# main_scheme.net
KiCad netlist of a schematic drawn in Altium Designer
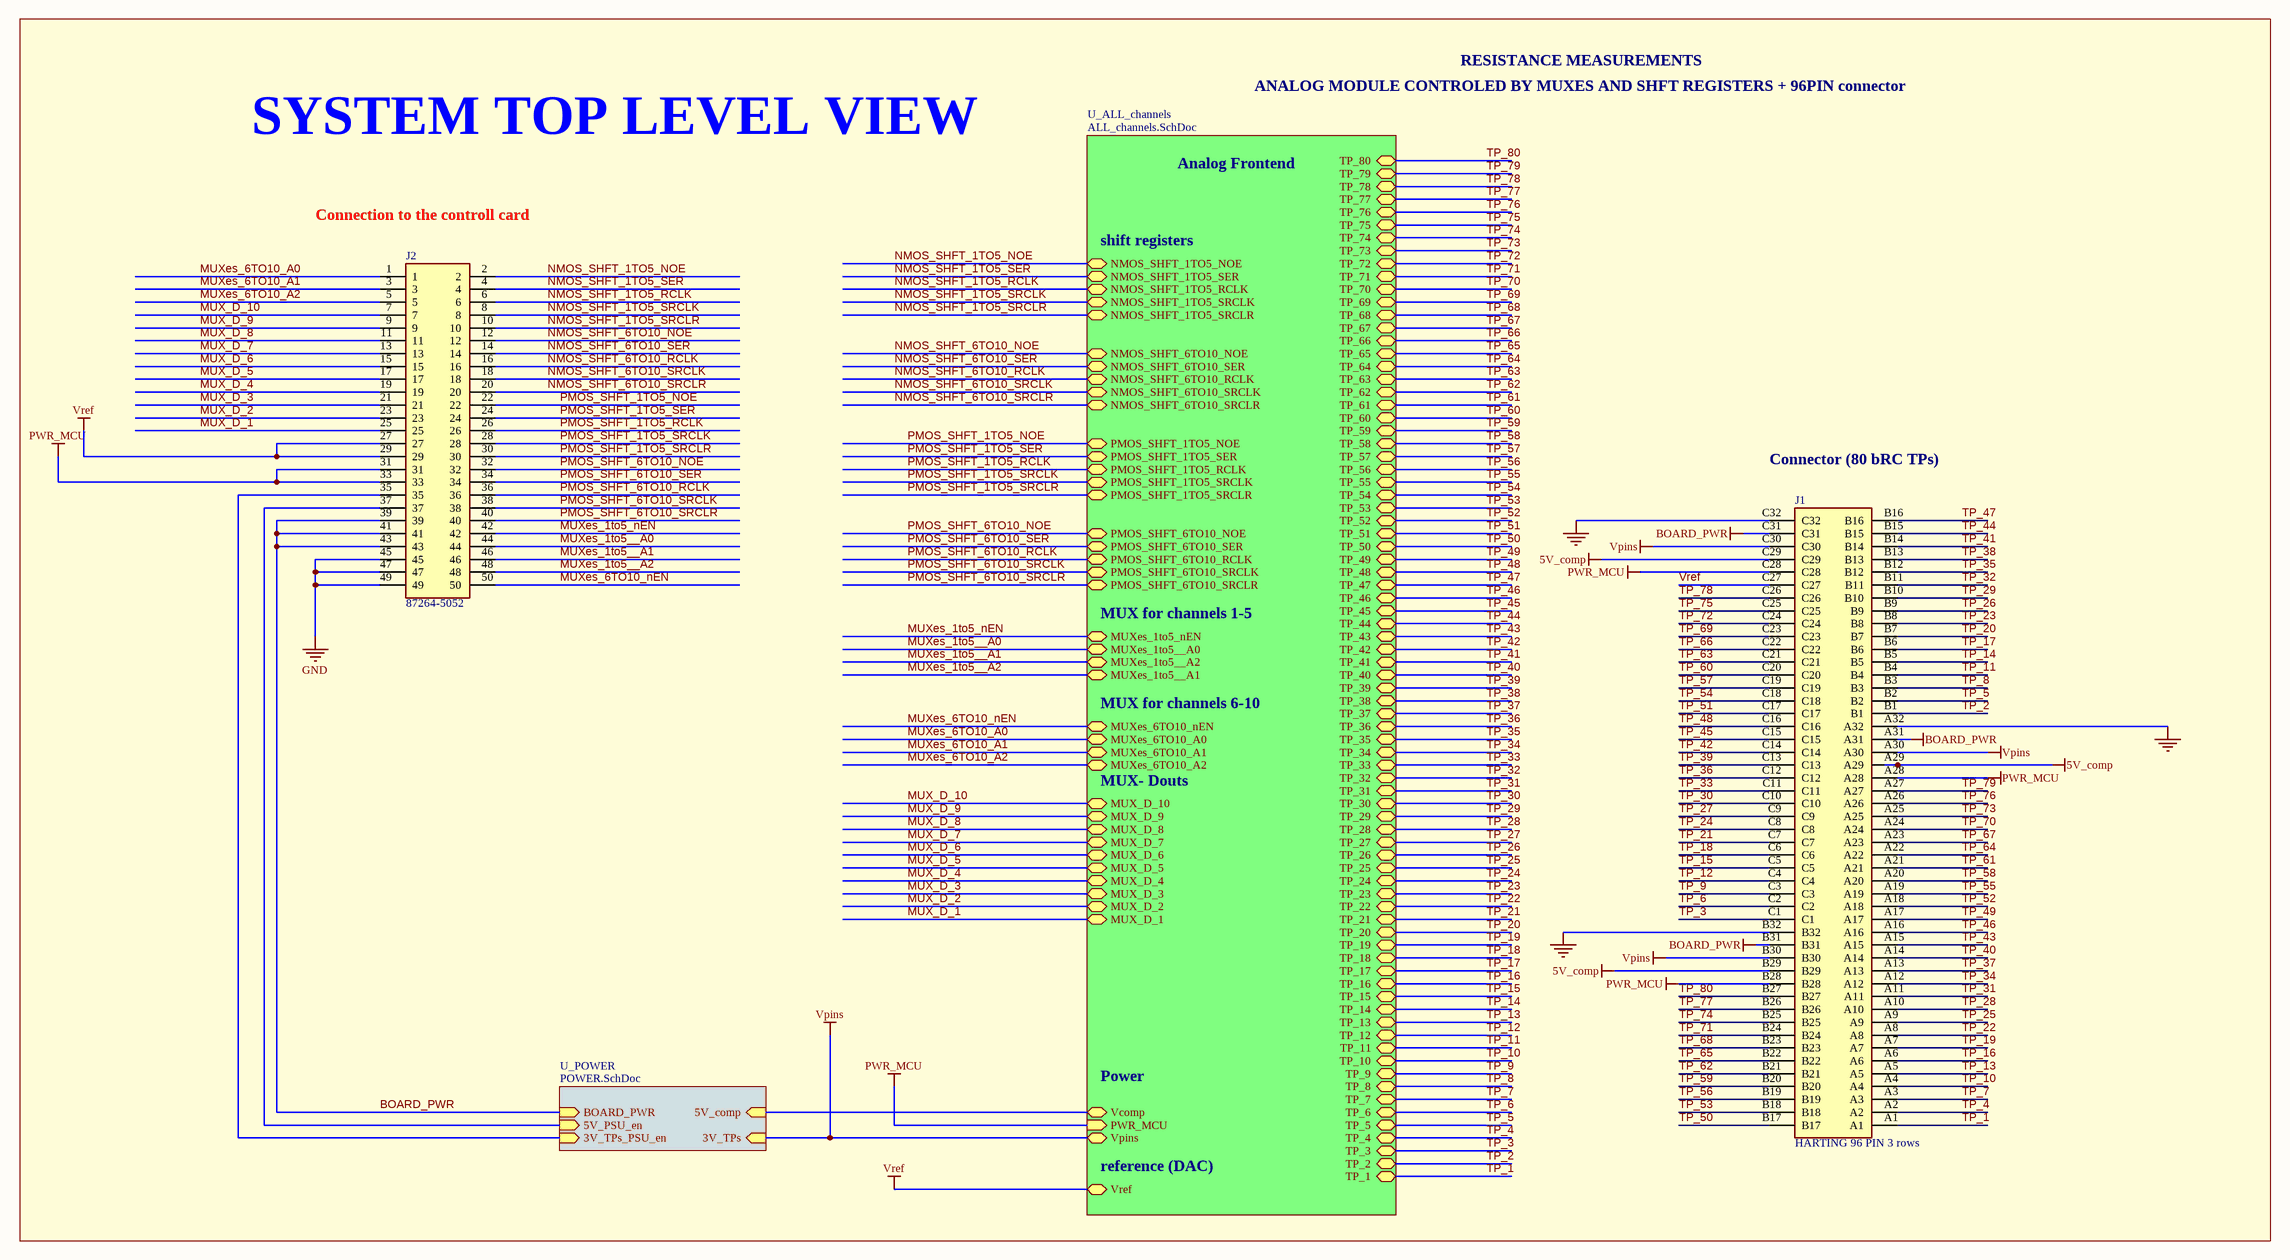
[diagram p0: main_scheme.SchDoc]

(export (version "E")
  (design (tool "Eeschema 10.0.6"))
  (components
    (comp (ref "J1")
      (value "HARTING 96 PIN 3 rows")
      (footprint "09033966921 - NO_3D")
      (description "Connector")
      (fields
        (field (name "MANUFACTURER_PART_NUMBER") "09033966921")
        (field (name "MOUSER PART NUMBER") "617-09-03-396-6921")
      )
      (libsource (lib "Schlib1") (part "HARTING 96 PIN 3 rows"))
    )
    (comp (ref "J2")
      (value "87264-5052")
      (footprint "SamacSys:872645052")
      (description "Connector")
      (fields (field (name "MOUSER PART NUMBER") "538-87264-5052"))
      (libsource (lib "*") (part "87264-5052"))
    )
  )
  (nets
    (net (code "1") (name "/3V_TPs_PSU_en") (class "Default")
      (node (ref "J2") (pin "35") (pinfunction "35_35") (pintype "passive"))
    )
    (net (code "2") (name "/5V_PSU_en") (class "Default")
      (node (ref "J2") (pin "37") (pinfunction "37_37") (pintype "passive"))
    )
    (net (code "4") (name "/MUX_D_1") (class "Default")
      (node (ref "J2") (pin "25") (pinfunction "25_25") (pintype "passive"))
    )
    (net (code "5") (name "/MUX_D_2") (class "Default")
      (node (ref "J2") (pin "23") (pinfunction "23_23") (pintype "passive"))
    )
    (net (code "6") (name "/MUX_D_3") (class "Default")
      (node (ref "J2") (pin "21") (pinfunction "21_21") (pintype "passive"))
    )
    (net (code "7") (name "/MUX_D_4") (class "Default")
      (node (ref "J2") (pin "19") (pinfunction "19_19") (pintype "passive"))
    )
    (net (code "8") (name "/MUX_D_5") (class "Default")
      (node (ref "J2") (pin "17") (pinfunction "17_17") (pintype "passive"))
    )
    (net (code "9") (name "/MUX_D_6") (class "Default")
      (node (ref "J2") (pin "15") (pinfunction "15_15") (pintype "passive"))
    )
    (net (code "10") (name "/MUX_D_7") (class "Default")
      (node (ref "J2") (pin "13") (pinfunction "13_13") (pintype "passive"))
    )
    (net (code "11") (name "/MUX_D_8") (class "Default")
      (node (ref "J2") (pin "11") (pinfunction "11_11") (pintype "passive"))
    )
    (net (code "12") (name "/MUX_D_9") (class "Default")
      (node (ref "J2") (pin "9") (pinfunction "9_9") (pintype "passive"))
    )
    (net (code "13") (name "/MUX_D_10") (class "Default")
      (node (ref "J2") (pin "7") (pinfunction "7_7") (pintype "passive"))
    )
    (net (code "14") (name "/MUXes_1to5__A0") (class "Default")
      (node (ref "J2") (pin "44") (pinfunction "44_44") (pintype "passive"))
    )
    (net (code "15") (name "/MUXes_1to5__A1") (class "Default")
      (node (ref "J2") (pin "46") (pinfunction "46_46") (pintype "passive"))
    )
    (net (code "16") (name "/MUXes_1to5__A2") (class "Default")
      (node (ref "J2") (pin "48") (pinfunction "48_48") (pintype "passive"))
    )
    (net (code "17") (name "/MUXes_1to5_nEN") (class "Default")
      (node (ref "J2") (pin "42") (pinfunction "42_42") (pintype "passive"))
    )
    (net (code "18") (name "/MUXes_6TO10_A0") (class "Default")
      (node (ref "J2") (pin "1") (pinfunction "1_1") (pintype "passive"))
    )
    (net (code "19") (name "/MUXes_6TO10_A1") (class "Default")
      (node (ref "J2") (pin "3") (pinfunction "3_3") (pintype "passive"))
    )
    (net (code "20") (name "/MUXes_6TO10_A2") (class "Default")
      (node (ref "J2") (pin "5") (pinfunction "5_5") (pintype "passive"))
    )
    (net (code "21") (name "/MUXes_6TO10_nEN") (class "Default")
      (node (ref "J2") (pin "50") (pinfunction "50_50") (pintype "passive"))
    )
    (net (code "22") (name "/NMOS_SHFT_1TO5_NOE") (class "Default")
      (node (ref "J2") (pin "2") (pinfunction "2_2") (pintype "passive"))
    )
    (net (code "23") (name "/NMOS_SHFT_1TO5_RCLK") (class "Default")
      (node (ref "J2") (pin "6") (pinfunction "6_6") (pintype "passive"))
    )
    (net (code "24") (name "/NMOS_SHFT_1TO5_SER") (class "Default")
      (node (ref "J2") (pin "4") (pinfunction "4_4") (pintype "passive"))
    )
    (net (code "25") (name "/NMOS_SHFT_1TO5_SRCLK") (class "Default")
      (node (ref "J2") (pin "8") (pinfunction "8_8") (pintype "passive"))
    )
    (net (code "26") (name "/NMOS_SHFT_1TO5_SRCLR") (class "Default")
      (node (ref "J2") (pin "10") (pinfunction "10_10") (pintype "passive"))
    )
    (net (code "27") (name "/NMOS_SHFT_6TO10_NOE") (class "Default")
      (node (ref "J2") (pin "12") (pinfunction "12_12") (pintype "passive"))
    )
    (net (code "28") (name "/NMOS_SHFT_6TO10_RCLK") (class "Default")
      (node (ref "J2") (pin "16") (pinfunction "16_16") (pintype "passive"))
    )
    (net (code "29") (name "/NMOS_SHFT_6TO10_SER") (class "Default")
      (node (ref "J2") (pin "14") (pinfunction "14_14") (pintype "passive"))
    )
    (net (code "30") (name "/NMOS_SHFT_6TO10_SRCLK") (class "Default")
      (node (ref "J2") (pin "18") (pinfunction "18_18") (pintype "passive"))
    )
    (net (code "31") (name "/NMOS_SHFT_6TO10_SRCLR") (class "Default")
      (node (ref "J2") (pin "20") (pinfunction "20_20") (pintype "passive"))
    )
    (net (code "32") (name "/PMOS_SHFT_1TO5_NOE") (class "Default")
      (node (ref "J2") (pin "22") (pinfunction "22_22") (pintype "passive"))
    )
    (net (code "33") (name "/PMOS_SHFT_1TO5_RCLK") (class "Default")
      (node (ref "J2") (pin "26") (pinfunction "26_26") (pintype "passive"))
    )
    (net (code "34") (name "/PMOS_SHFT_1TO5_SER") (class "Default")
      (node (ref "J2") (pin "24") (pinfunction "24_24") (pintype "passive"))
    )
    (net (code "35") (name "/PMOS_SHFT_1TO5_SRCLK") (class "Default")
      (node (ref "J2") (pin "28") (pinfunction "28_28") (pintype "passive"))
    )
    (net (code "36") (name "/PMOS_SHFT_1TO5_SRCLR") (class "Default")
      (node (ref "J2") (pin "30") (pinfunction "30_30") (pintype "passive"))
    )
    (net (code "37") (name "/PMOS_SHFT_6TO10_NOE") (class "Default")
      (node (ref "J2") (pin "32") (pinfunction "32_32") (pintype "passive"))
    )
    (net (code "38") (name "/PMOS_SHFT_6TO10_RCLK") (class "Default")
      (node (ref "J2") (pin "36") (pinfunction "36_36") (pintype "passive"))
    )
    (net (code "39") (name "/PMOS_SHFT_6TO10_SER") (class "Default")
      (node (ref "J2") (pin "34") (pinfunction "34_34") (pintype "passive"))
    )
    (net (code "40") (name "/PMOS_SHFT_6TO10_SRCLK") (class "Default")
      (node (ref "J2") (pin "38") (pinfunction "38_38") (pintype "passive"))
    )
    (net (code "41") (name "/PMOS_SHFT_6TO10_SRCLR") (class "Default")
      (node (ref "J2") (pin "40") (pinfunction "40_40") (pintype "passive"))
    )
    (net (code "42") (name "/TP_1") (class "Default")
      (node (ref "J1") (pin "A1") (pinfunction "A1_A1") (pintype "passive"))
    )
    (net (code "43") (name "/TP_2") (class "Default")
      (node (ref "J1") (pin "B1") (pinfunction "B1_B1") (pintype "passive"))
    )
    (net (code "44") (name "/TP_3") (class "Default")
      (node (ref "J1") (pin "C1") (pinfunction "C1_C1") (pintype "passive"))
    )
    (net (code "45") (name "/TP_4") (class "Default")
      (node (ref "J1") (pin "A2") (pinfunction "A2_A2") (pintype "passive"))
    )
    (net (code "46") (name "/TP_5") (class "Default")
      (node (ref "J1") (pin "B2") (pinfunction "B2_B2") (pintype "passive"))
    )
    (net (code "47") (name "/TP_6") (class "Default")
      (node (ref "J1") (pin "C2") (pinfunction "C2_C2") (pintype "passive"))
    )
    (net (code "48") (name "/TP_7") (class "Default")
      (node (ref "J1") (pin "A3") (pinfunction "A3_A3") (pintype "passive"))
    )
    (net (code "49") (name "/TP_8") (class "Default")
      (node (ref "J1") (pin "B3") (pinfunction "B3_B3") (pintype "passive"))
    )
    (net (code "50") (name "/TP_9") (class "Default")
      (node (ref "J1") (pin "C3") (pinfunction "C3_C3") (pintype "passive"))
    )
    (net (code "51") (name "/TP_10") (class "Default")
      (node (ref "J1") (pin "A4") (pinfunction "A4_A4") (pintype "passive"))
    )
    (net (code "52") (name "/TP_11") (class "Default")
      (node (ref "J1") (pin "B4") (pinfunction "B4_B4") (pintype "passive"))
    )
    (net (code "53") (name "/TP_12") (class "Default")
      (node (ref "J1") (pin "C4") (pinfunction "C4_C4") (pintype "passive"))
    )
    (net (code "54") (name "/TP_13") (class "Default")
      (node (ref "J1") (pin "A5") (pinfunction "A5_A5") (pintype "passive"))
    )
    (net (code "55") (name "/TP_14") (class "Default")
      (node (ref "J1") (pin "B5") (pinfunction "B5_B5") (pintype "passive"))
    )
    (net (code "56") (name "/TP_15") (class "Default")
      (node (ref "J1") (pin "C5") (pinfunction "C5_C5") (pintype "passive"))
    )
    (net (code "57") (name "/TP_16") (class "Default")
      (node (ref "J1") (pin "A6") (pinfunction "A6_A6") (pintype "passive"))
    )
    (net (code "58") (name "/TP_17") (class "Default")
      (node (ref "J1") (pin "B6") (pinfunction "B6_B6") (pintype "passive"))
    )
    (net (code "59") (name "/TP_18") (class "Default")
      (node (ref "J1") (pin "C6") (pinfunction "C6_C6") (pintype "passive"))
    )
    (net (code "60") (name "/TP_19") (class "Default")
      (node (ref "J1") (pin "A7") (pinfunction "A7_A7") (pintype "passive"))
    )
    (net (code "61") (name "/TP_20") (class "Default")
      (node (ref "J1") (pin "B7") (pinfunction "B7_B7") (pintype "passive"))
    )
    (net (code "62") (name "/TP_21") (class "Default")
      (node (ref "J1") (pin "C7") (pinfunction "C7_C7") (pintype "passive"))
    )
    (net (code "63") (name "/TP_22") (class "Default")
      (node (ref "J1") (pin "A8") (pinfunction "A8_A8") (pintype "passive"))
    )
    (net (code "64") (name "/TP_23") (class "Default")
      (node (ref "J1") (pin "B8") (pinfunction "B8_B8") (pintype "passive"))
    )
    (net (code "65") (name "/TP_24") (class "Default")
      (node (ref "J1") (pin "C8") (pinfunction "C8_C8") (pintype "passive"))
    )
    (net (code "66") (name "/TP_25") (class "Default")
      (node (ref "J1") (pin "A9") (pinfunction "A9_A9") (pintype "passive"))
    )
    (net (code "67") (name "/TP_26") (class "Default")
      (node (ref "J1") (pin "B9") (pinfunction "B9_B9") (pintype "passive"))
    )
    (net (code "68") (name "/TP_27") (class "Default")
      (node (ref "J1") (pin "C9") (pinfunction "C9_C9") (pintype "passive"))
    )
    (net (code "69") (name "/TP_28") (class "Default")
      (node (ref "J1") (pin "A10") (pinfunction "A10_A10") (pintype "passive"))
    )
    (net (code "70") (name "/TP_29") (class "Default")
      (node (ref "J1") (pin "B10") (pinfunction "B10_B10") (pintype "passive"))
    )
    (net (code "71") (name "/TP_30") (class "Default")
      (node (ref "J1") (pin "C10") (pinfunction "C10_C10") (pintype "passive"))
    )
    (net (code "72") (name "/TP_31") (class "Default")
      (node (ref "J1") (pin "A11") (pinfunction "A11_A11") (pintype "passive"))
    )
    (net (code "73") (name "/TP_32") (class "Default")
      (node (ref "J1") (pin "B11") (pinfunction "B11_B11") (pintype "passive"))
    )
    (net (code "74") (name "/TP_33") (class "Default")
      (node (ref "J1") (pin "C11") (pinfunction "C11_C11") (pintype "passive"))
    )
    (net (code "75") (name "/TP_34") (class "Default")
      (node (ref "J1") (pin "A12") (pinfunction "A12_A12") (pintype "passive"))
    )
    (net (code "76") (name "/TP_35") (class "Default")
      (node (ref "J1") (pin "B12") (pinfunction "B12_B12") (pintype "passive"))
    )
    (net (code "77") (name "/TP_36") (class "Default")
      (node (ref "J1") (pin "C12") (pinfunction "C12_C12") (pintype "passive"))
    )
    (net (code "78") (name "/TP_37") (class "Default")
      (node (ref "J1") (pin "A13") (pinfunction "A13_A13") (pintype "passive"))
    )
    (net (code "79") (name "/TP_38") (class "Default")
      (node (ref "J1") (pin "B13") (pinfunction "B13_B13") (pintype "passive"))
    )
    (net (code "80") (name "/TP_39") (class "Default")
      (node (ref "J1") (pin "C13") (pinfunction "C13_C13") (pintype "passive"))
    )
    (net (code "81") (name "/TP_40") (class "Default")
      (node (ref "J1") (pin "A14") (pinfunction "A14_A14") (pintype "passive"))
    )
    (net (code "82") (name "/TP_41") (class "Default")
      (node (ref "J1") (pin "B14") (pinfunction "B14_B14") (pintype "passive"))
    )
    (net (code "83") (name "/TP_42") (class "Default")
      (node (ref "J1") (pin "C14") (pinfunction "C14_C14") (pintype "passive"))
    )
    (net (code "84") (name "/TP_43") (class "Default")
      (node (ref "J1") (pin "A15") (pinfunction "A15_A15") (pintype "passive"))
    )
    (net (code "85") (name "/TP_44") (class "Default")
      (node (ref "J1") (pin "B15") (pinfunction "B15_B15") (pintype "passive"))
    )
    (net (code "86") (name "/TP_45") (class "Default")
      (node (ref "J1") (pin "C15") (pinfunction "C15_C15") (pintype "passive"))
    )
    (net (code "87") (name "/TP_46") (class "Default")
      (node (ref "J1") (pin "A16") (pinfunction "A16_A16") (pintype "passive"))
    )
    (net (code "88") (name "/TP_47") (class "Default")
      (node (ref "J1") (pin "B16") (pinfunction "B16_B16") (pintype "passive"))
    )
    (net (code "89") (name "/TP_48") (class "Default")
      (node (ref "J1") (pin "C16") (pinfunction "C16_C16") (pintype "passive"))
    )
    (net (code "90") (name "/TP_49") (class "Default")
      (node (ref "J1") (pin "A17") (pinfunction "A17_A17") (pintype "passive"))
    )
    (net (code "91") (name "/TP_50") (class "Default")
      (node (ref "J1") (pin "B17") (pinfunction "B17_B17") (pintype "passive"))
    )
    (net (code "92") (name "/TP_51") (class "Default")
      (node (ref "J1") (pin "C17") (pinfunction "C17_C17") (pintype "passive"))
    )
    (net (code "93") (name "/TP_52") (class "Default")
      (node (ref "J1") (pin "A18") (pinfunction "A18_A18") (pintype "passive"))
    )
    (net (code "94") (name "/TP_53") (class "Default")
      (node (ref "J1") (pin "B18") (pinfunction "B18_B18") (pintype "passive"))
    )
    (net (code "95") (name "/TP_54") (class "Default")
      (node (ref "J1") (pin "C18") (pinfunction "C18_C18") (pintype "passive"))
    )
    (net (code "96") (name "/TP_55") (class "Default")
      (node (ref "J1") (pin "A19") (pinfunction "A19_A19") (pintype "passive"))
    )
    (net (code "97") (name "/TP_56") (class "Default")
      (node (ref "J1") (pin "B19") (pinfunction "B19_B19") (pintype "passive"))
    )
    (net (code "98") (name "/TP_57") (class "Default")
      (node (ref "J1") (pin "C19") (pinfunction "C19_C19") (pintype "passive"))
    )
    (net (code "99") (name "/TP_58") (class "Default")
      (node (ref "J1") (pin "A20") (pinfunction "A20_A20") (pintype "passive"))
    )
    (net (code "100") (name "/TP_59") (class "Default")
      (node (ref "J1") (pin "B20") (pinfunction "B20_B20") (pintype "passive"))
    )
    (net (code "101") (name "/TP_60") (class "Default")
      (node (ref "J1") (pin "C20") (pinfunction "C20_C20") (pintype "passive"))
    )
    (net (code "102") (name "/TP_61") (class "Default")
      (node (ref "J1") (pin "A21") (pinfunction "A21_A21") (pintype "passive"))
    )
    (net (code "103") (name "/TP_62") (class "Default")
      (node (ref "J1") (pin "B21") (pinfunction "B21_B21") (pintype "passive"))
    )
    (net (code "104") (name "/TP_63") (class "Default")
      (node (ref "J1") (pin "C21") (pinfunction "C21_C21") (pintype "passive"))
    )
    (net (code "105") (name "/TP_64") (class "Default")
      (node (ref "J1") (pin "A22") (pinfunction "A22_A22") (pintype "passive"))
    )
    (net (code "106") (name "/TP_65") (class "Default")
      (node (ref "J1") (pin "B22") (pinfunction "B22_B22") (pintype "passive"))
    )
    (net (code "107") (name "/TP_66") (class "Default")
      (node (ref "J1") (pin "C22") (pinfunction "C22_C22") (pintype "passive"))
    )
    (net (code "108") (name "/TP_67") (class "Default")
      (node (ref "J1") (pin "A23") (pinfunction "A23_A23") (pintype "passive"))
    )
    (net (code "109") (name "/TP_68") (class "Default")
      (node (ref "J1") (pin "B23") (pinfunction "B23_B23") (pintype "passive"))
    )
    (net (code "110") (name "/TP_69") (class "Default")
      (node (ref "J1") (pin "C23") (pinfunction "C23_C23") (pintype "passive"))
    )
    (net (code "111") (name "/TP_70") (class "Default")
      (node (ref "J1") (pin "A24") (pinfunction "A24_A24") (pintype "passive"))
    )
    (net (code "112") (name "/TP_71") (class "Default")
      (node (ref "J1") (pin "B24") (pinfunction "B24_B24") (pintype "passive"))
    )
    (net (code "113") (name "/TP_72") (class "Default")
      (node (ref "J1") (pin "C24") (pinfunction "C24_C24") (pintype "passive"))
    )
    (net (code "114") (name "/TP_73") (class "Default")
      (node (ref "J1") (pin "A25") (pinfunction "A25_A25") (pintype "passive"))
    )
    (net (code "115") (name "/TP_74") (class "Default")
      (node (ref "J1") (pin "B25") (pinfunction "B25_B25") (pintype "passive"))
    )
    (net (code "116") (name "/TP_75") (class "Default")
      (node (ref "J1") (pin "C25") (pinfunction "C25_C25") (pintype "passive"))
    )
    (net (code "117") (name "/TP_76") (class "Default")
      (node (ref "J1") (pin "A26") (pinfunction "A26_A26") (pintype "passive"))
    )
    (net (code "118") (name "/TP_77") (class "Default")
      (node (ref "J1") (pin "B26") (pinfunction "B26_B26") (pintype "passive"))
    )
    (net (code "119") (name "/TP_78") (class "Default")
      (node (ref "J1") (pin "C26") (pinfunction "C26_C26") (pintype "passive"))
    )
    (net (code "120") (name "/TP_79") (class "Default")
      (node (ref "J1") (pin "A27") (pinfunction "A27_A27") (pintype "passive"))
    )
    (net (code "121") (name "/TP_80") (class "Default")
      (node (ref "J1") (pin "B27") (pinfunction "B27_B27") (pintype "passive"))
    )
    (net (code "122") (name "5V_comp") (class "Default")
      (node (ref "J1") (pin "A29") (pinfunction "A29_A29") (pintype "passive"))
      (node (ref "J1") (pin "B29") (pinfunction "B29_B29") (pintype "passive"))
      (node (ref "J1") (pin "C29") (pinfunction "C29_C29") (pintype "passive"))
    )
    (net (code "123") (name "BOARD_PWR") (class "Default")
      (node (ref "J1") (pin "A31") (pinfunction "A31_A31") (pintype "passive"))
      (node (ref "J1") (pin "B31") (pinfunction "B31_B31") (pintype "passive"))
      (node (ref "J1") (pin "C31") (pinfunction "C31_C31") (pintype "passive"))
      (node (ref "J2") (pin "39") (pinfunction "39_39") (pintype "passive"))
      (node (ref "J2") (pin "41") (pinfunction "41_41") (pintype "passive"))
      (node (ref "J2") (pin "43") (pinfunction "43_43") (pintype "passive"))
    )
    (net (code "124") (name "GND") (class "Default")
      (node (ref "J1") (pin "A32") (pinfunction "A32_A32") (pintype "passive"))
      (node (ref "J1") (pin "B32") (pinfunction "B32_B32") (pintype "passive"))
      (node (ref "J1") (pin "C32") (pinfunction "C32_C32") (pintype "passive"))
      (node (ref "J2") (pin "45") (pinfunction "45_45") (pintype "passive"))
      (node (ref "J2") (pin "47") (pinfunction "47_47") (pintype "passive"))
      (node (ref "J2") (pin "49") (pinfunction "49_49") (pintype "passive"))
    )
    (net (code "125") (name "PWR_MCU") (class "Default")
      (node (ref "J1") (pin "A28") (pinfunction "A28_A28") (pintype "passive"))
      (node (ref "J1") (pin "B28") (pinfunction "B28_B28") (pintype "passive"))
      (node (ref "J1") (pin "C28") (pinfunction "C28_C28") (pintype "passive"))
      (node (ref "J2") (pin "31") (pinfunction "31_31") (pintype "passive"))
      (node (ref "J2") (pin "33") (pinfunction "33_33") (pintype "passive"))
    )
    (net (code "126") (name "Vpins") (class "Default")
      (node (ref "J1") (pin "A30") (pinfunction "A30_A30") (pintype "passive"))
      (node (ref "J1") (pin "B30") (pinfunction "B30_B30") (pintype "passive"))
      (node (ref "J1") (pin "C30") (pinfunction "C30_C30") (pintype "passive"))
    )
    (net (code "127") (name "Vref") (class "Default")
      (node (ref "J1") (pin "C27") (pinfunction "C27_C27") (pintype "passive"))
      (node (ref "J2") (pin "27") (pinfunction "27_27") (pintype "passive"))
      (node (ref "J2") (pin "29") (pinfunction "29_29") (pintype "passive"))
    )
  )
)
